# 2_powerSupply.net
KiCad netlist of a schematic drawn in Altium Designer
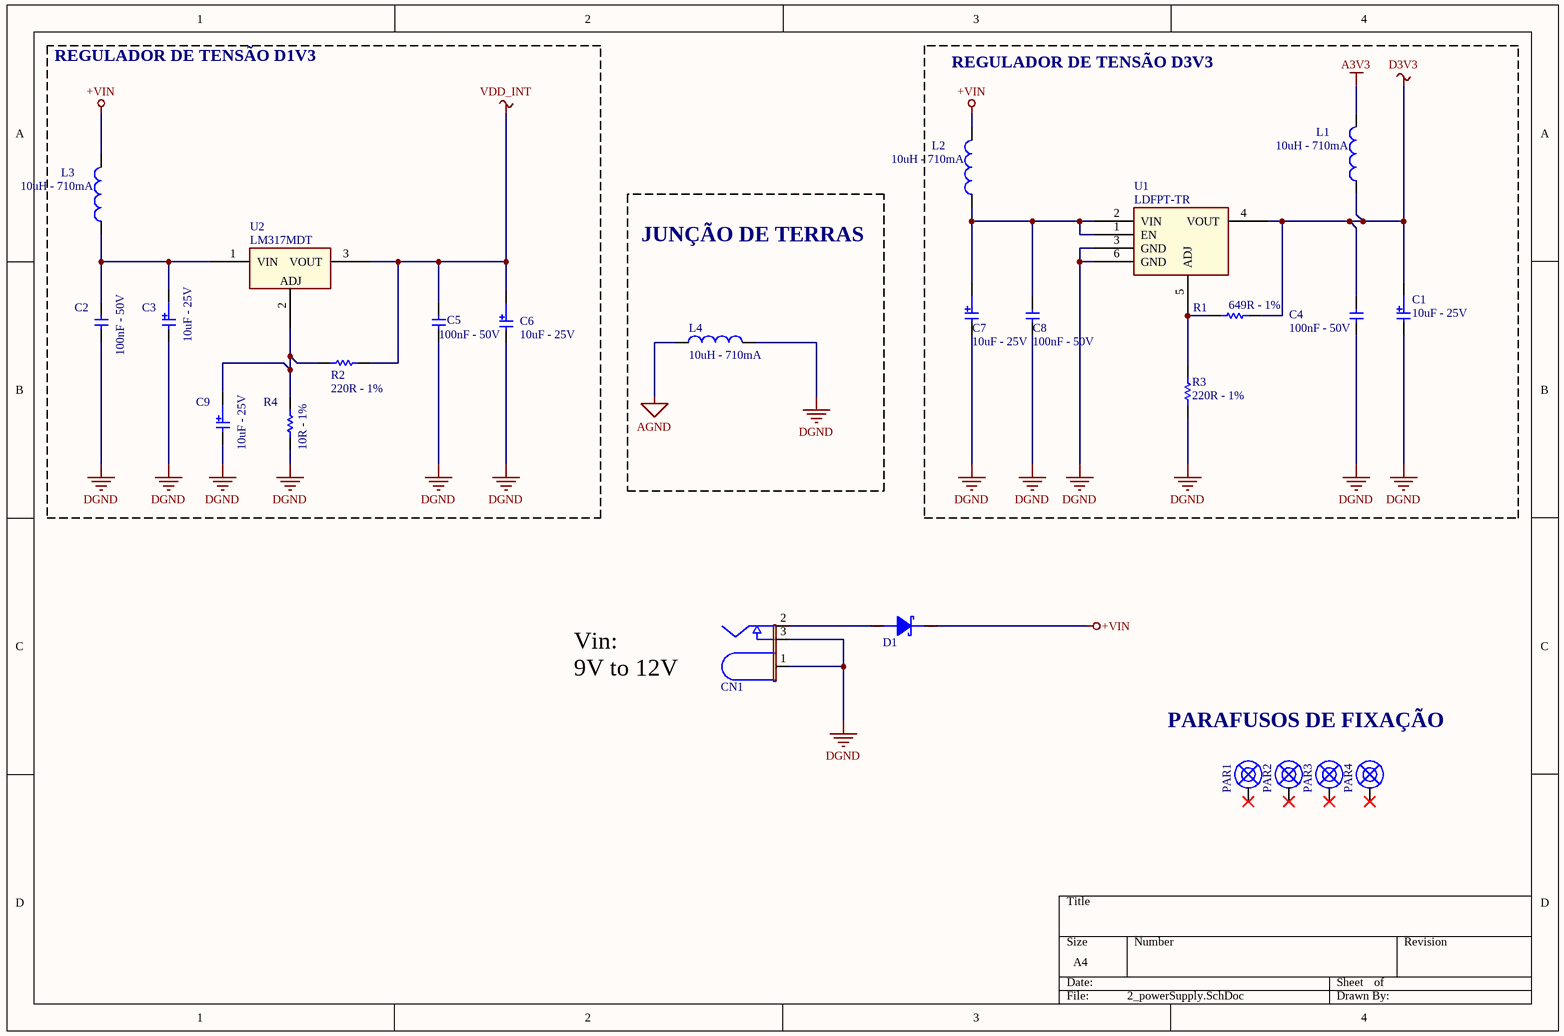
[diagram p0: 2_powerSupply.SchDoc]

(export (version "E")
  (design (tool "Eeschema 10.0.6"))
  (components
    (comp (ref "C1")
      (value "10uF - 25V - 10% - SMD2412 - 5430")
      (footprint "SMD2412-CAP")
      (description "Capacitor 10uF, SDM TANTALUM")
      (fields
        (field (name "MANUFACTURER") "AVX")
        (field (name "PARTNUMBER") "TBJC106K025LBSB0024")
        (field (name "VALOR") "10uF - 25V")
      )
      (libsource (lib "Capacitor_smd") (part "10uF - 25V - 10% - SMD2412 - 5430"))
    )
    (comp (ref "C2")
      (value "Capacitor 100nF - 50V")
      (footprint "SMD0805-CAP")
      (description "Capacitor 100nF, SMD 0805")
      (fields
        (field (name "VOLTAGE") "CMAX")
        (field (name "PARTNUMBER") "08055G104ZAT2A")
        (field (name "VALOR") "100nF - 50V")
      )
      (libsource (lib "CAPACITOR_SMD") (part "Capacitor 100nF - 50V"))
    )
    (comp (ref "C3")
      (value "10uF - 25V - 10% - SMD2412 - 5430")
      (footprint "SMD2412-CAP")
      (description "Capacitor 10uF, SDM TANTALUM")
      (fields
        (field (name "MANUFACTURER") "AVX")
        (field (name "PARTNUMBER") "TBJC106K025LBSB0024")
        (field (name "VALOR") "10uF - 25V")
      )
      (libsource (lib "Capacitor_smd") (part "10uF - 25V - 10% - SMD2412 - 5430"))
    )
    (comp (ref "C4")
      (value "Capacitor 100nF - 50V")
      (footprint "SMD0805-CAP")
      (description "Capacitor 100nF, SMD 0805")
      (fields
        (field (name "VOLTAGE") "CMAX")
        (field (name "PARTNUMBER") "08055G104ZAT2A")
        (field (name "VALOR") "100nF - 50V")
      )
      (libsource (lib "CAPACITOR_SMD") (part "Capacitor 100nF - 50V"))
    )
    (comp (ref "C5")
      (value "Capacitor 100nF - 50V")
      (footprint "SMD0805-CAP")
      (description "Capacitor 100nF, SMD 0805")
      (fields
        (field (name "VOLTAGE") "CMAX")
        (field (name "PARTNUMBER") "08055G104ZAT2A")
        (field (name "VALOR") "100nF - 50V")
      )
      (libsource (lib "CAPACITOR_SMD") (part "Capacitor 100nF - 50V"))
    )
    (comp (ref "C6")
      (value "10uF - 25V - 10% - SMD2412 - 5430")
      (footprint "SMD2412-CAP")
      (description "Capacitor 10uF, SDM TANTALUM")
      (fields
        (field (name "MANUFACTURER") "AVX")
        (field (name "PARTNUMBER") "TBJC106K025LBSB0024")
        (field (name "VALOR") "10uF - 25V")
      )
      (libsource (lib "Capacitor_smd") (part "10uF - 25V - 10% - SMD2412 - 5430"))
    )
    (comp (ref "C7")
      (value "10uF - 25V - 10% - SMD2412 - 5430")
      (footprint "SMD2412-CAP")
      (description "Capacitor 10uF, SDM TANTALUM")
      (fields
        (field (name "MANUFACTURER") "AVX")
        (field (name "PARTNUMBER") "TBJC106K025LBSB0024")
        (field (name "VALOR") "10uF - 25V")
      )
      (libsource (lib "Capacitor_smd") (part "10uF - 25V - 10% - SMD2412 - 5430"))
    )
    (comp (ref "C8")
      (value "Capacitor 100nF - 50V")
      (footprint "SMD0805-CAP")
      (description "Capacitor 100nF, SMD 0805")
      (fields
        (field (name "VOLTAGE") "CMAX")
        (field (name "PARTNUMBER") "08055G104ZAT2A")
        (field (name "VALOR") "100nF - 50V")
      )
      (libsource (lib "CAPACITOR_SMD") (part "Capacitor 100nF - 50V"))
    )
    (comp (ref "C9")
      (value "10uF - 25V - 10% - SMD2412 - 5430")
      (footprint "SMD2412-CAP")
      (description "Capacitor 10uF, SDM TANTALUM")
      (fields
        (field (name "MANUFACTURER") "AVX")
        (field (name "PARTNUMBER") "TBJC106K025LBSB0024")
        (field (name "VALOR") "10uF - 25V")
      )
      (libsource (lib "Capacitor_smd") (part "10uF - 25V - 10% - SMD2412 - 5430"))
    )
    (comp (ref "CN1")
      (value "Conector POWER JACK 2.5MM")
      (footprint "RAPC712X")
      (fields (field (name "PARTNUMBER") "RAPC712X") (field (name "MANUFACTURER") "SWITCHCRAFT"))
      (libsource (lib "Conector") (part "CNC POWER JACK 2.5MM - 4414"))
    )
    (comp (ref "D1")
      (value "Diodo B2100-13-F (SMB)")
      (footprint "SMB")
      (fields (field (name "PARTNUMBER") "B2100-13-F") (field (name "MANUFACTURER") "DIODES INC"))
      (libsource (lib "Não_padronizados") (part "Diodo B2100-13-F (SMB)"))
    )
    (comp (ref "L1")
      (value "Indutor 10uH 710mA SMD")
      (footprint "WE-TPC-S")
      (fields
        (field (name "PARTNUMBER") "LQH3NPN100NJ0L")
        (field (name "MANUFACTURER") "MURATA")
        (field (name "VALOR") "10uH - 710mA")
      )
      (libsource (lib "Eletromagnetico") (part "10uH - 710mA - SMD - 3058"))
    )
    (comp (ref "L2")
      (value "Indutor 10uH 710mA SMD")
      (footprint "WE-TPC-S")
      (fields
        (field (name "PARTNUMBER") "LQH3NPN100NJ0L")
        (field (name "MANUFACTURER") "MURATA")
        (field (name "VALOR") "10uH - 710mA")
      )
      (libsource (lib "Eletromagnetico") (part "10uH - 710mA - SMD - 3058"))
    )
    (comp (ref "L3")
      (value "Indutor 10uH 710mA SMD")
      (footprint "WE-TPC-S")
      (fields
        (field (name "PARTNUMBER") "LQH3NPN100NJ0L")
        (field (name "MANUFACTURER") "MURATA")
        (field (name "VALOR") "10uH - 710mA")
      )
      (libsource (lib "Eletromagnetico") (part "10uH - 710mA - SMD - 3058"))
    )
    (comp (ref "L4")
      (value "Indutor 10uH 710mA SMD")
      (footprint "WE-TPC-S")
      (fields
        (field (name "PARTNUMBER") "LQH3NPN100NJ0L")
        (field (name "MANUFACTURER") "MURATA")
        (field (name "VALOR") "10uH - 710mA")
      )
      (libsource (lib "Eletromagnetico") (part "10uH - 710mA - SMD - 3058"))
    )
    (comp (ref "PAR1")
      (value "Parafuso M3 - 1295")
      (footprint "FURO/142/240/M4/CHASSI")
      (description "Parafuso M3")
      (libsource (lib "PARAFUSO") (part "Parafuso M3 - 1295"))
    )
    (comp (ref "PAR2")
      (value "Parafuso M3 - 1295")
      (footprint "FURO/142/240/M4/CHASSI")
      (description "Parafuso M3")
      (libsource (lib "PARAFUSO") (part "Parafuso M3 - 1295"))
    )
    (comp (ref "PAR3")
      (value "Parafuso M3 - 1295")
      (footprint "FURO/142/240/M4/CHASSI")
      (description "Parafuso M3")
      (libsource (lib "PARAFUSO") (part "Parafuso M3 - 1295"))
    )
    (comp (ref "PAR4")
      (value "Parafuso M3 - 1295")
      (footprint "FURO/142/240/M4/CHASSI")
      (description "Parafuso M3")
      (libsource (lib "PARAFUSO") (part "Parafuso M3 - 1295"))
    )
    (comp (ref "R1")
      (value "649R- 1% - 0805 - 466")
      (footprint "SMD0805")
      (description "Resistor 649R, 1%, SMD 0805")
      (fields
        (field (name "PARTNUMBER") "RC2012F6490CS")
        (field (name "MANUFACTURER") "SAMSUNG")
        (field (name "VALOR") "649R - 1%")
      )
      (libsource (lib "Resistor_smd") (part "649R - 1% - 0805 - 466"))
    )
    (comp (ref "R2")
      (value "220R - 1% - 0805 - 381")
      (footprint "SMD0805")
      (description "Resistor 220R, 1%, SMD 0805")
      (fields
        (field (name "PARTNUMBER") "ERJ-6ENF2200V")
        (field (name "MANUFACTURER") "SAMSUNG")
        (field (name "VALOR") "220R - 1%")
      )
      (libsource (lib "Resistor_smd") (part "220R - 1% - 0805 - 381"))
    )
    (comp (ref "R3")
      (value "220R - 1% - 0805 - 381")
      (footprint "SMD0805")
      (description "Resistor 220R, 1%, SMD 0805")
      (fields
        (field (name "PARTNUMBER") "ERJ-6ENF2200V")
        (field (name "MANUFACTURER") "SAMSUNG")
        (field (name "VALOR") "220R - 1%")
      )
      (libsource (lib "Resistor_smd") (part "220R - 1% - 0805 - 381"))
    )
    (comp (ref "R4")
      (value "10R - 1% - 0805 - 344")
      (footprint "SMD0805")
      (description "Resistor 10R, 1%, SMD 0805")
      (fields
        (field (name "PARTNUMBER") "RC2012F10R0CS")
        (field (name "MANUFACTURER") "SANSUNG")
        (field (name "VALOR") "10R - 1%")
      )
      (libsource (lib "Resistor_smd") (part "10R - 1% - 0805 - 344"))
    )
    (comp (ref "U1")
      (value "CI LDFPT-TR")
      (footprint "PPAK-5")
      (fields
        (field (name "MANUFACTURER") "ST MICROELETRONICS")
        (field (name "PARTNUMBER") "LDFPT-TR")
        (field (name "VALOR") "LDFPT-TR")
      )
      (libsource (lib "CI_SMD") (part "CI LDFPT-TR"))
    )
    (comp (ref "U2")
      (value "LM317MDT (TO252) 713")
      (footprint "TO252")
      (description "CI LM317MDT")
      (fields
        (field (name "MANUFACTURER") "NATIONAL")
        (field (name "PARTNUMBER") "LM317MDT")
        (field (name "VALOR") "LM317MDT")
      )
      (libsource (lib "CI_smd") (part "LM317MDT (TO252) 713"))
    )
  )
  (nets
    (net (code "1") (name "+VIN") (class "Default")
      (node (ref "D1") (pin "2") (pinfunction "K_2") (pintype "passive"))
      (node (ref "L2") (pin "2") (pinfunction "2_2") (pintype "passive"))
      (node (ref "L3") (pin "2") (pinfunction "2_2") (pintype "passive"))
    )
    (net (code "2") (name "A3V3") (class "Default")
      (node (ref "L1") (pin "2") (pinfunction "2_2") (pintype "passive"))
    )
    (net (code "3") (name "AGND") (class "Default")
      (node (ref "L4") (pin "1") (pinfunction "1_1") (pintype "passive"))
    )
    (net (code "4") (name "D3V3") (class "Default")
      (node (ref "C1") (pin "1") (pinfunction "+_1") (pintype "passive"))
      (node (ref "C4") (pin "1") (pinfunction "1_1") (pintype "passive"))
      (node (ref "L1") (pin "1") (pinfunction "1_1") (pintype "passive"))
      (node (ref "R1") (pin "2") (pinfunction "2_2") (pintype "passive"))
      (node (ref "U1") (pin "4") (pinfunction "VOUT_4") (pintype "passive"))
    )
    (net (code "5") (name "DGND") (class "Default")
      (node (ref "C1") (pin "2") (pinfunction "-_2") (pintype "passive"))
      (node (ref "C2") (pin "2") (pinfunction "2_2") (pintype "passive"))
      (node (ref "C3") (pin "2") (pinfunction "-_2") (pintype "passive"))
      (node (ref "C4") (pin "2") (pinfunction "2_2") (pintype "passive"))
      (node (ref "C5") (pin "2") (pinfunction "2_2") (pintype "passive"))
      (node (ref "C6") (pin "2") (pinfunction "-_2") (pintype "passive"))
      (node (ref "C7") (pin "2") (pinfunction "-_2") (pintype "passive"))
      (node (ref "C8") (pin "2") (pinfunction "2_2") (pintype "passive"))
      (node (ref "C9") (pin "2") (pinfunction "-_2") (pintype "passive"))
      (node (ref "CN1") (pin "1") (pinfunction "1_1") (pintype "passive"))
      (node (ref "CN1") (pin "3") (pinfunction "3_3") (pintype "passive"))
      (node (ref "L4") (pin "2") (pinfunction "2_2") (pintype "passive"))
      (node (ref "R3") (pin "1") (pinfunction "1_1") (pintype "passive"))
      (node (ref "R4") (pin "1") (pinfunction "1_1") (pintype "passive"))
      (node (ref "U1") (pin "3") (pinfunction "GND_3") (pintype "passive"))
      (node (ref "U1") (pin "6") (pinfunction "GND_6") (pintype "passive"))
    )
    (net (code "6") (name "Net-(C3-+)") (class "Default")
      (node (ref "C2") (pin "1") (pinfunction "1_1") (pintype "passive"))
      (node (ref "C3") (pin "1") (pinfunction "+_1") (pintype "passive"))
      (node (ref "L3") (pin "1") (pinfunction "1_1") (pintype "passive"))
      (node (ref "U2") (pin "1") (pinfunction "VIN_1") (pintype "power_in"))
    )
    (net (code "7") (name "Net-(C7-+)") (class "Default")
      (node (ref "C7") (pin "1") (pinfunction "+_1") (pintype "passive"))
      (node (ref "C8") (pin "1") (pinfunction "1_1") (pintype "passive"))
      (node (ref "L2") (pin "1") (pinfunction "1_1") (pintype "passive"))
      (node (ref "U1") (pin "1") (pinfunction "EN_1") (pintype "passive"))
      (node (ref "U1") (pin "2") (pinfunction "VIN_2") (pintype "passive"))
    )
    (net (code "8") (name "Net-(C9-+)") (class "Default")
      (node (ref "C9") (pin "1") (pinfunction "+_1") (pintype "passive"))
      (node (ref "R2") (pin "1") (pinfunction "1_1") (pintype "passive"))
      (node (ref "R4") (pin "2") (pinfunction "2_2") (pintype "passive"))
      (node (ref "U2") (pin "2") (pinfunction "ADJ_2") (pintype "passive"))
    )
    (net (code "9") (name "Net-(D1-A)") (class "Default")
      (node (ref "CN1") (pin "2") (pinfunction "2_2") (pintype "passive"))
      (node (ref "D1") (pin "1") (pinfunction "A_1") (pintype "passive"))
    )
    (net (code "10") (name "Net-(U1-ADJ)") (class "Default")
      (node (ref "R1") (pin "1") (pinfunction "1_1") (pintype "passive"))
      (node (ref "R3") (pin "2") (pinfunction "2_2") (pintype "passive"))
      (node (ref "U1") (pin "5") (pinfunction "ADJ_5") (pintype "passive"))
    )
    (net (code "11") (name "VDD_INT") (class "Default")
      (node (ref "C5") (pin "1") (pinfunction "1_1") (pintype "passive"))
      (node (ref "C6") (pin "1") (pinfunction "+_1") (pintype "passive"))
      (node (ref "R2") (pin "2") (pinfunction "2_2") (pintype "passive"))
      (node (ref "U2") (pin "3") (pinfunction "VOUT_3") (pintype "passive"))
    )
    (net (code "12") (name "unconnected-(PAR1-Pad1)") (class "Default")
      (node (ref "PAR1") (pin "1") (pinfunction "1_1") (pintype "passive+no_connect"))
    )
    (net (code "13") (name "unconnected-(PAR2-Pad1)") (class "Default")
      (node (ref "PAR2") (pin "1") (pinfunction "1_1") (pintype "passive+no_connect"))
    )
    (net (code "14") (name "unconnected-(PAR3-Pad1)") (class "Default")
      (node (ref "PAR3") (pin "1") (pinfunction "1_1") (pintype "passive+no_connect"))
    )
    (net (code "15") (name "unconnected-(PAR4-Pad1)") (class "Default")
      (node (ref "PAR4") (pin "1") (pinfunction "1_1") (pintype "passive+no_connect"))
    )
  )
)
